# UPM_pcb_v1-0.net
KiCad netlist of a schematic drawn in EAGLE
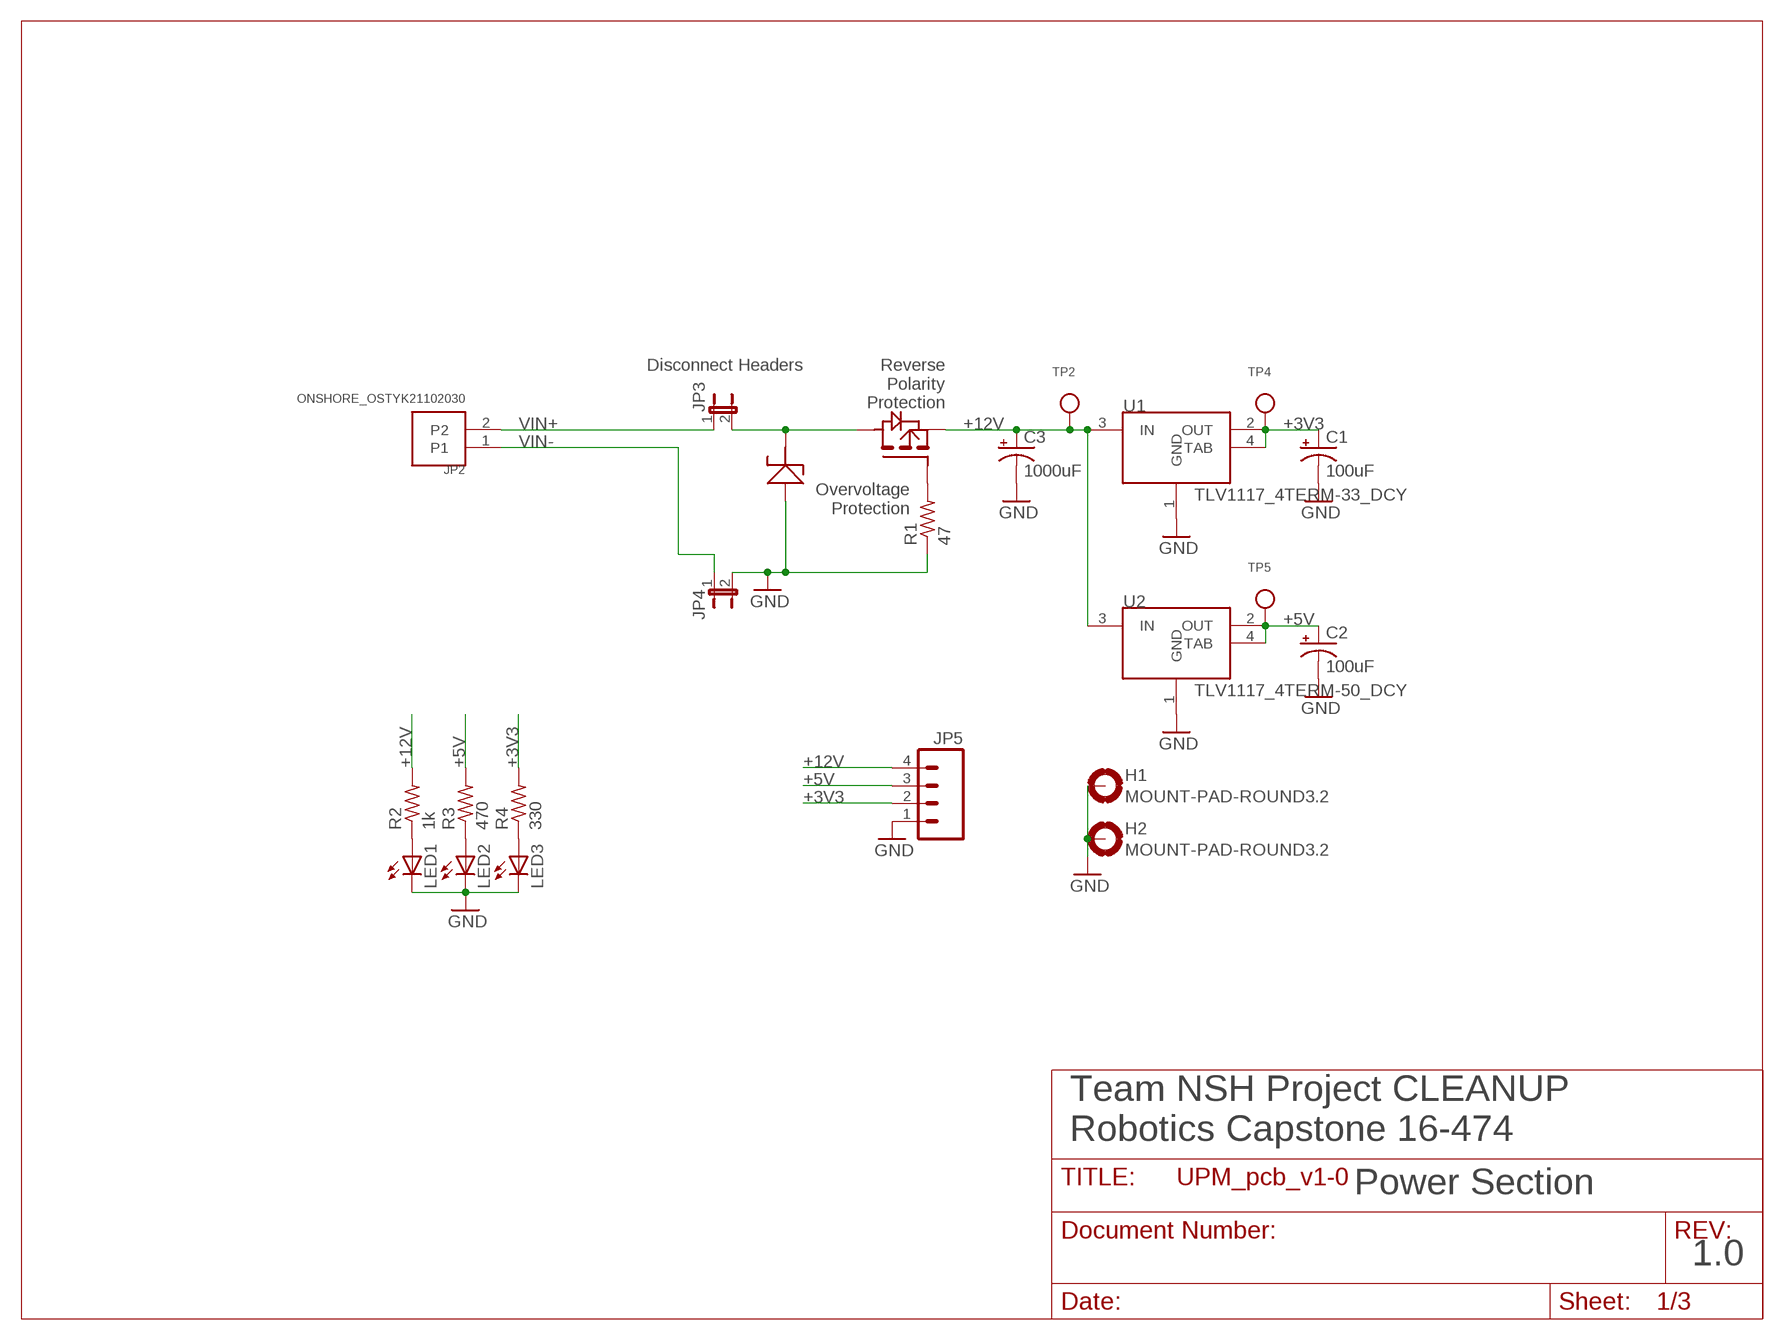
[diagram p0: schematic, sheet 1]
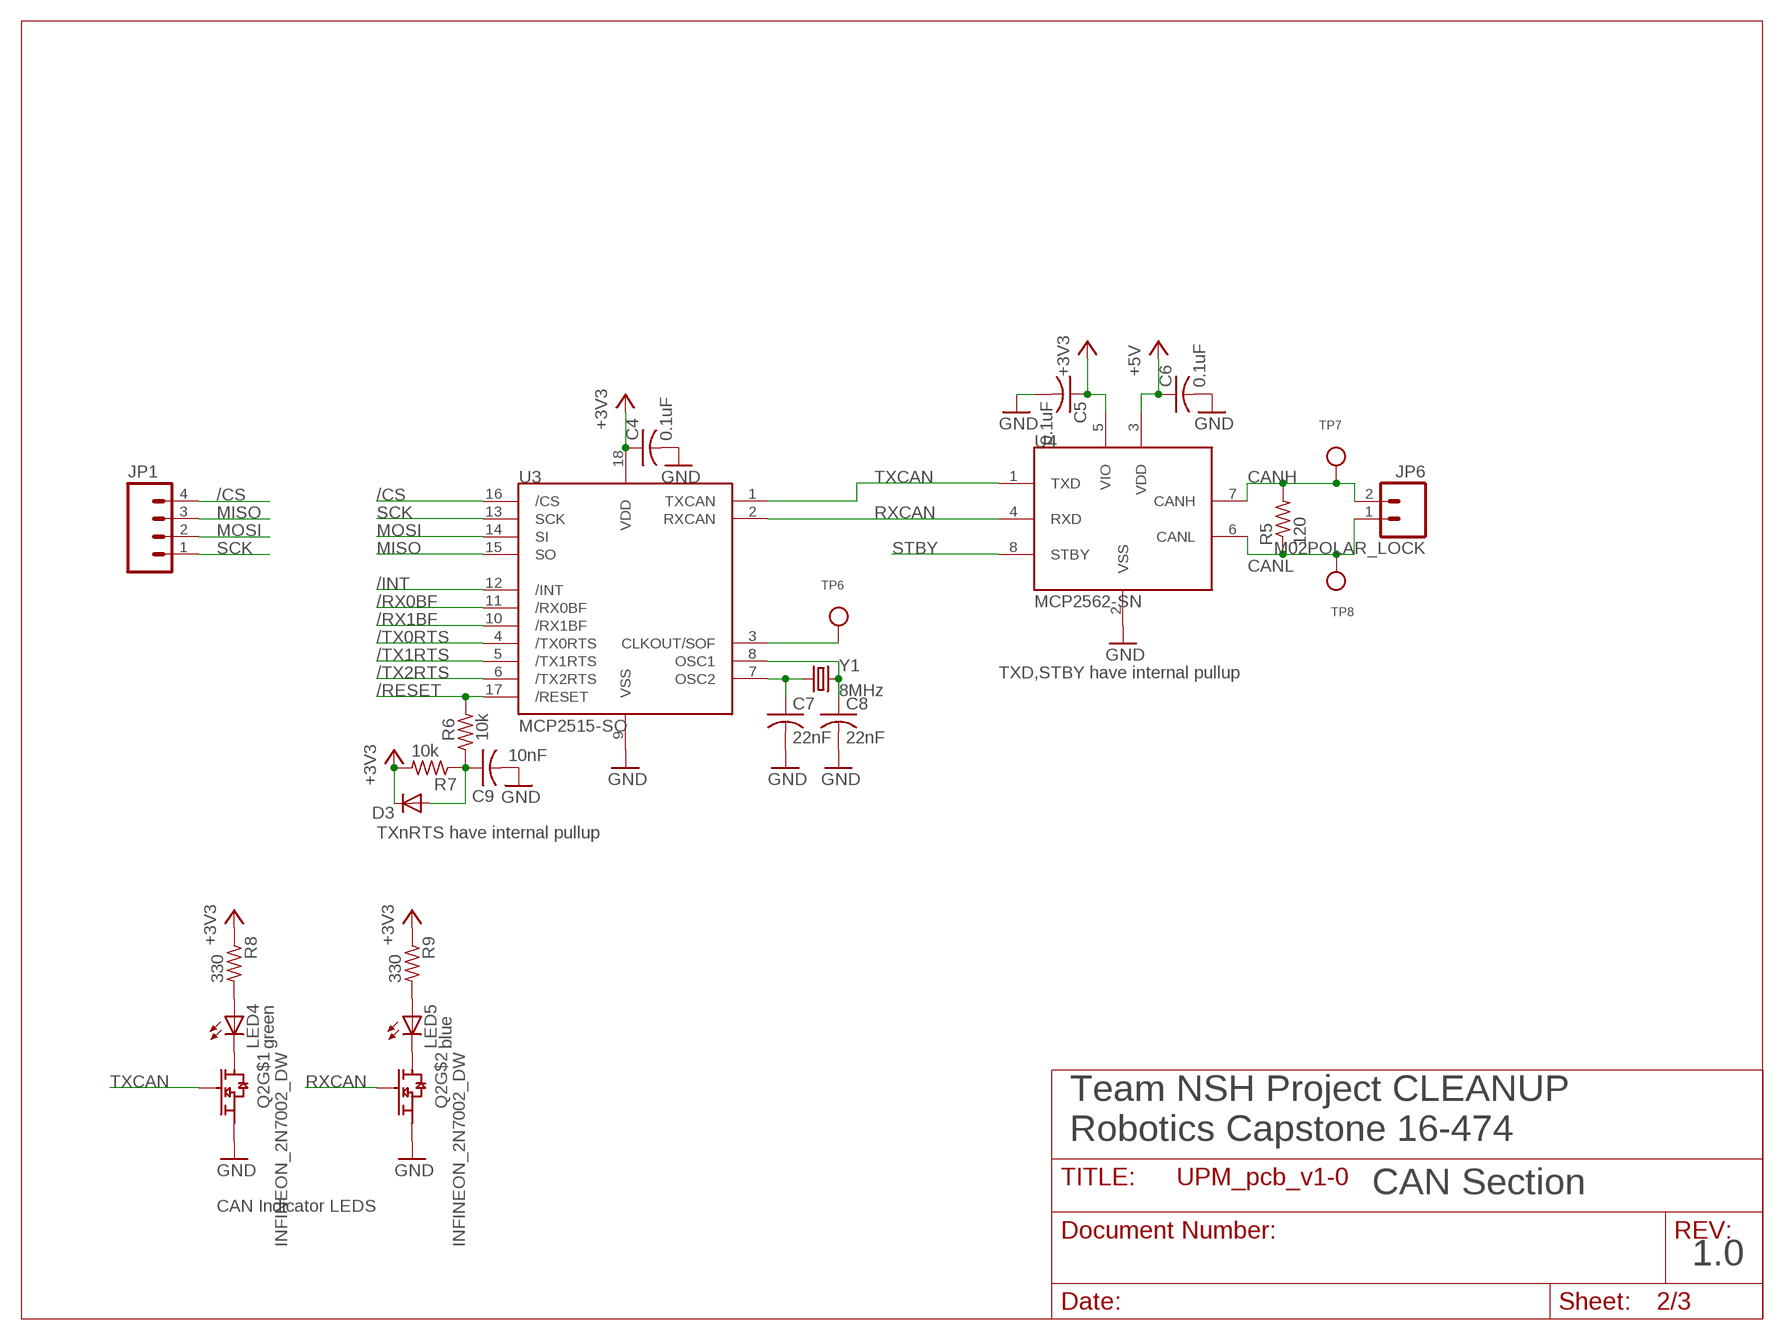
[diagram p1: schematic, sheet 2]
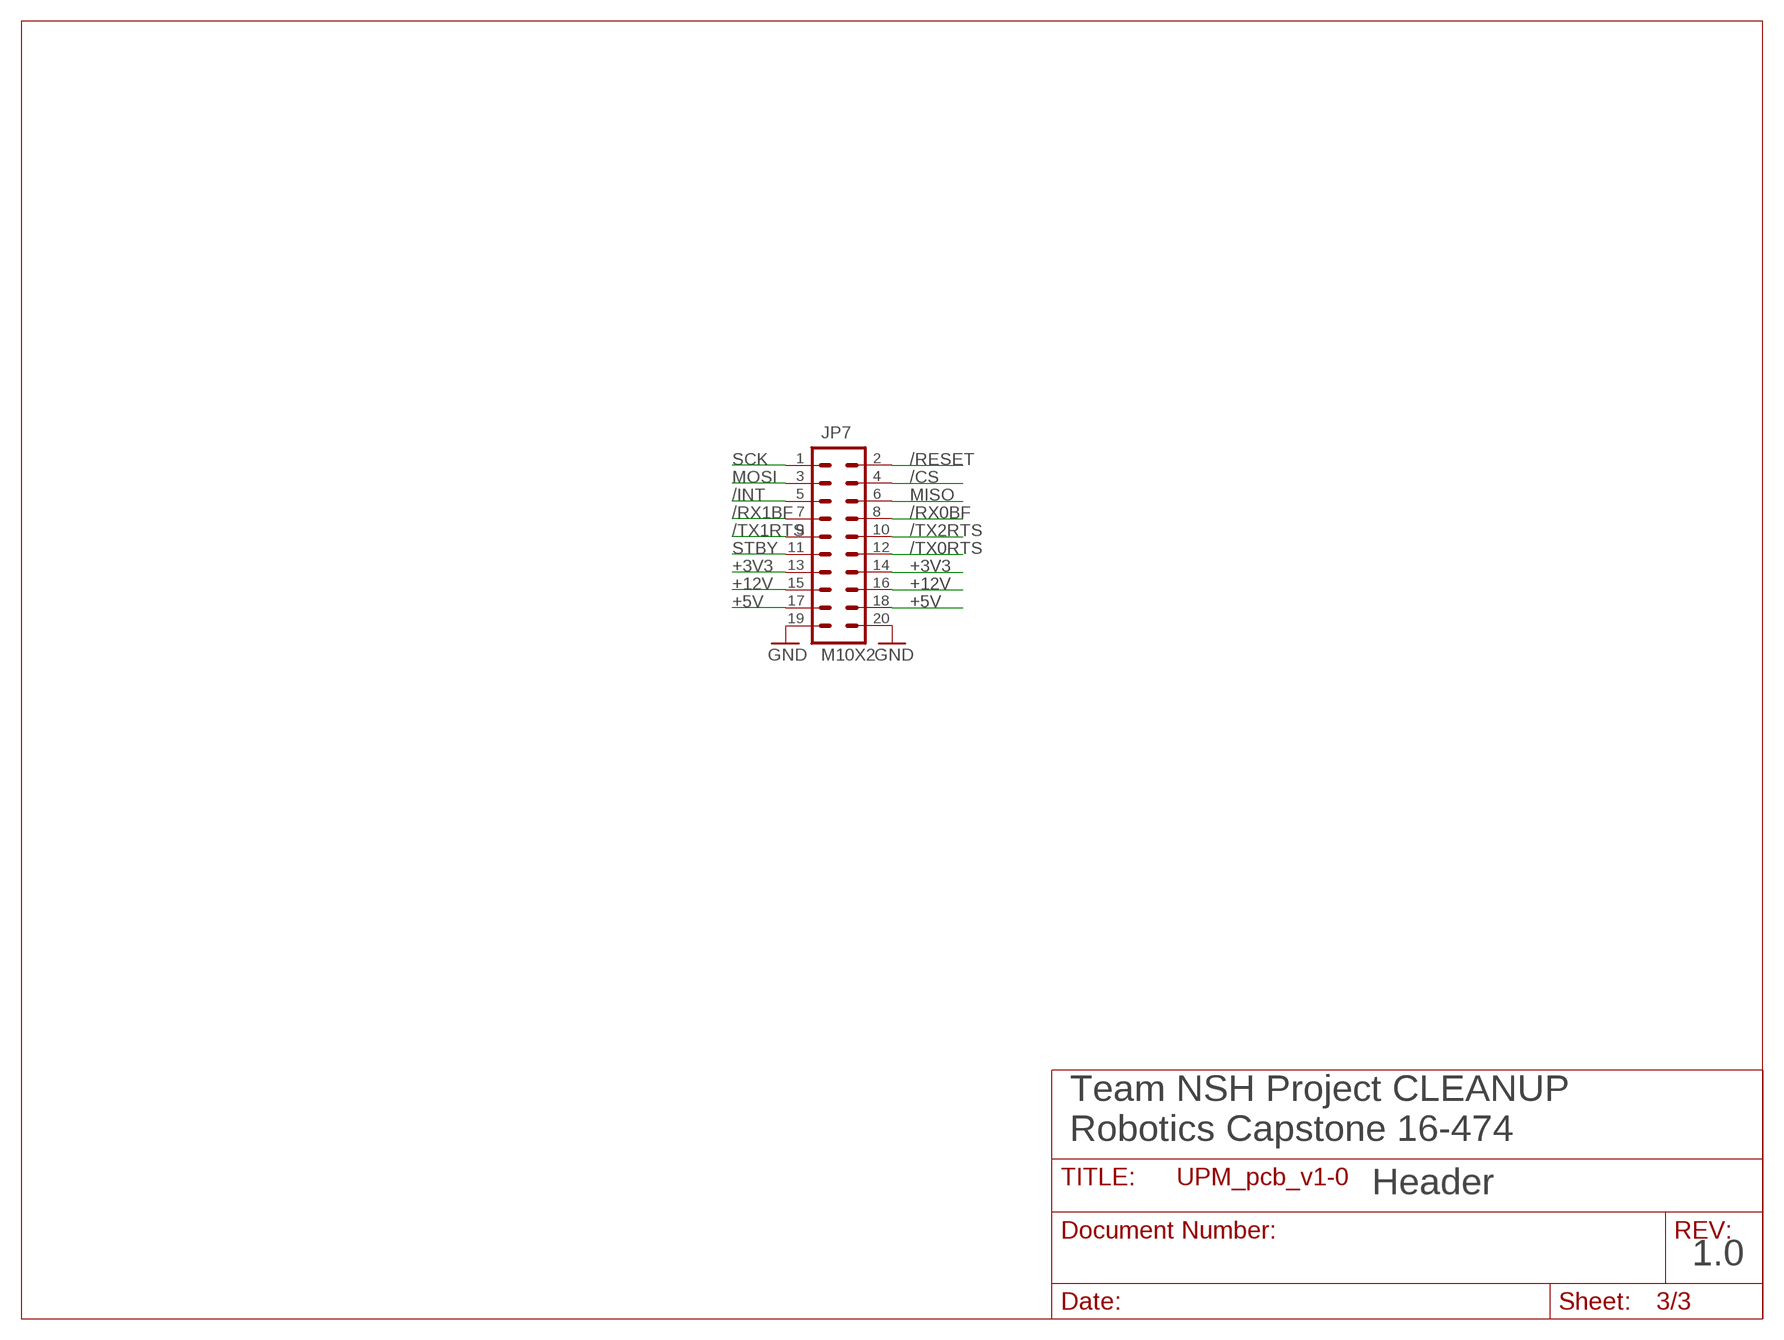
[diagram p2: schematic, sheet 3]

(export (version "E")
  (design (tool "Eeschema 10.0.6"))
  (components
    (comp (ref "C1")
      (value "100uF")
      (footprint "eagle-import:E2,5-5")
      (libsource (lib "eagle-import") (part "CPOL-USE2.5-5"))
    )
    (comp (ref "C2")
      (value "100uF")
      (footprint "eagle-import:E2,5-5")
      (libsource (lib "eagle-import") (part "CPOL-USE2.5-5"))
    )
    (comp (ref "C3")
      (value "1000uF")
      (footprint "eagle-import:E5-13")
      (libsource (lib "eagle-import") (part "CPOL-USE5-13"))
    )
    (comp (ref "D1")
      (value "VISHAY_SMA6F")
      (footprint "eagle-import:VSHY_DO-221AC")
      (libsource (lib "eagle-import") (part "VISHAY_SMA6F"))
    )
    (comp (ref "H1")
      (value "MOUNT-PAD-ROUND3.2")
      (footprint "eagle-import:3,2-PAD")
      (libsource (lib "eagle-import") (part "MOUNT-PAD-ROUND3.2"))
    )
    (comp (ref "H2")
      (value "MOUNT-PAD-ROUND3.2")
      (footprint "eagle-import:3,2-PAD")
      (libsource (lib "eagle-import") (part "MOUNT-PAD-ROUND3.2"))
    )
    (comp (ref "JP2")
      (value "ONSHORE_OSTYK21102030")
      (footprint "eagle-import:ONSHORE_OSTYK21102030")
      (libsource (lib "eagle-import") (part "ONSHORE_OSTYK21102030"))
    )
    (comp (ref "JP3")
      (value "JUMPER2")
      (footprint "eagle-import:JUMPER2")
      (libsource (lib "eagle-import") (part "JUMPER2"))
    )
    (comp (ref "JP4")
      (value "JUMPER2")
      (footprint "eagle-import:JUMPER2")
      (libsource (lib "eagle-import") (part "JUMPER2"))
    )
    (comp (ref "JP5")
      (value "M04LOCK")
      (footprint "eagle-import:1X04_LOCK")
      (libsource (lib "eagle-import") (part "M04LOCK"))
    )
    (comp (ref "LED1")
      (value "LED0603")
      (footprint "eagle-import:LED-0603")
      (libsource (lib "eagle-import") (part "LED0603"))
    )
    (comp (ref "LED2")
      (value "LED0603")
      (footprint "eagle-import:LED-0603")
      (libsource (lib "eagle-import") (part "LED0603"))
    )
    (comp (ref "LED3")
      (value "LED0603")
      (footprint "eagle-import:LED-0603")
      (libsource (lib "eagle-import") (part "LED0603"))
    )
    (comp (ref "Q1")
      (value "DMP4047SK3")
      (footprint "eagle-import:DIODES_TO252")
      (libsource (lib "eagle-import") (part "DMP4047SK3"))
    )
    (comp (ref "R1")
      (value "47")
      (footprint "eagle-import:R0603")
      (libsource (lib "eagle-import") (part "R-US_R0603"))
    )
    (comp (ref "R2")
      (value "1k")
      (footprint "eagle-import:R0603")
      (libsource (lib "eagle-import") (part "R-US_R0603"))
    )
    (comp (ref "R3")
      (value "470")
      (footprint "eagle-import:R0603")
      (libsource (lib "eagle-import") (part "R-US_R0603"))
    )
    (comp (ref "R4")
      (value "330")
      (footprint "eagle-import:R0603")
      (libsource (lib "eagle-import") (part "R-US_R0603"))
    )
    (comp (ref "TP2")
      (value "TESTPOINT0.1\"")
      (footprint "eagle-import:1X01_ROUND")
      (libsource (lib "eagle-import") (part "TESTPOINT0.1{dblquote}"))
    )
    (comp (ref "TP4")
      (value "TESTPOINT0.1\"")
      (footprint "eagle-import:1X01_ROUND")
      (libsource (lib "eagle-import") (part "TESTPOINT0.1{dblquote}"))
    )
    (comp (ref "TP5")
      (value "TESTPOINT0.1\"")
      (footprint "eagle-import:1X01_ROUND")
      (libsource (lib "eagle-import") (part "TESTPOINT0.1{dblquote}"))
    )
    (comp (ref "U1")
      (value "TLV1117_4TERM-33_DCY")
      (footprint "eagle-import:TI_SOT-223_DCY_R-PDSO-G4")
      (libsource (lib "eagle-import") (part "TLV1117_4TERM-33_DCY"))
    )
    (comp (ref "U2")
      (value "TLV1117_4TERM-50_DCY")
      (footprint "eagle-import:TI_SOT-223_DCY_R-PDSO-G4")
      (libsource (lib "eagle-import") (part "TLV1117_4TERM-50_DCY"))
    )
    (comp (ref "C4")
      (value "0.1uF")
      (footprint "eagle-import:C0603")
      (libsource (lib "eagle-import") (part "C-USC0603"))
    )
    (comp (ref "C5")
      (value "0.1uF")
      (footprint "eagle-import:C0603")
      (libsource (lib "eagle-import") (part "C-USC0603"))
    )
    (comp (ref "C6")
      (value "0.1uF")
      (footprint "eagle-import:C0603")
      (libsource (lib "eagle-import") (part "C-USC0603"))
    )
    (comp (ref "C7")
      (value "22nF")
      (footprint "eagle-import:C0603")
      (libsource (lib "eagle-import") (part "C-USC0603"))
    )
    (comp (ref "C8")
      (value "22nF")
      (footprint "eagle-import:C0603")
      (libsource (lib "eagle-import") (part "C-USC0603"))
    )
    (comp (ref "C9")
      (value "10nF")
      (footprint "eagle-import:C0603")
      (libsource (lib "eagle-import") (part "C-USC0603"))
    )
    (comp (ref "D3")
      (value "DIODE1N4148")
      (footprint "eagle-import:DIODE-1N4148")
      (libsource (lib "eagle-import") (part "DIODE1N4148"))
    )
    (comp (ref "JP1")
      (value "M04LOCK")
      (footprint "eagle-import:1X04_LOCK")
      (libsource (lib "eagle-import") (part "M04LOCK"))
    )
    (comp (ref "JP6")
      (value "M02POLAR_LOCK")
      (footprint "eagle-import:MOLEX-1X2_LOCK")
      (libsource (lib "eagle-import") (part "M02POLAR_LOCK"))
    )
    (comp (ref "LED4")
      (value "green")
      (footprint "eagle-import:LED-0603")
      (libsource (lib "eagle-import") (part "LED0603"))
    )
    (comp (ref "LED5")
      (value "blue")
      (footprint "eagle-import:LED-0603")
      (libsource (lib "eagle-import") (part "LED0603"))
    )
    (comp (ref "Q2")
      (value "INFINEON_2N7002_DW")
      (footprint "eagle-import:INFINEON_SOT363")
      (libsource (lib "eagle-import") (part "INFINEON_2N7002_DW"))
    )
    (comp (ref "R5")
      (value "120")
      (footprint "eagle-import:R0603")
      (libsource (lib "eagle-import") (part "R-US_R0603"))
    )
    (comp (ref "R6")
      (value "10k")
      (footprint "eagle-import:R0603")
      (libsource (lib "eagle-import") (part "R-US_R0603"))
    )
    (comp (ref "R7")
      (value "10k")
      (footprint "eagle-import:R0603")
      (libsource (lib "eagle-import") (part "R-US_R0603"))
    )
    (comp (ref "R8")
      (value "330")
      (footprint "eagle-import:R0603")
      (libsource (lib "eagle-import") (part "R-US_R0603"))
    )
    (comp (ref "R9")
      (value "330")
      (footprint "eagle-import:R0603")
      (libsource (lib "eagle-import") (part "R-US_R0603"))
    )
    (comp (ref "TP6")
      (value "TESTPOINT0.1\"")
      (footprint "eagle-import:1X01_ROUND")
      (libsource (lib "eagle-import") (part "TESTPOINT0.1{dblquote}"))
    )
    (comp (ref "TP7")
      (value "TESTPOINT0.1\"")
      (footprint "eagle-import:1X01_ROUND")
      (libsource (lib "eagle-import") (part "TESTPOINT0.1{dblquote}"))
    )
    (comp (ref "TP8")
      (value "TESTPOINT0.1\"")
      (footprint "eagle-import:1X01_ROUND")
      (libsource (lib "eagle-import") (part "TESTPOINT0.1{dblquote}"))
    )
    (comp (ref "U3")
      (value "MCP2515-SO")
      (footprint "eagle-import:MCP_SO_SOIC-18")
      (libsource (lib "eagle-import") (part "MCP2515-SO"))
    )
    (comp (ref "U4")
      (value "MCP2562-SN")
      (footprint "eagle-import:MCP_SN_SOIC-8")
      (libsource (lib "eagle-import") (part "MCP2562-SN"))
    )
    (comp (ref "Y1")
      (value "8MHz")
      (footprint "eagle-import:HC49U-V")
      (libsource (lib "eagle-import") (part "CRYSTALHC49UV"))
    )
    (comp (ref "JP7")
      (value "M10X2")
      (footprint "eagle-import:2X10")
      (libsource (lib "eagle-import") (part "M10X2"))
    )
  )
  (nets
    (net (code "1") (name "+3V3") (class "Default")
      (node (ref "C1") (pin "+") (pinfunction "+_+") (pintype "passive"))
      (node (ref "C4") (pin "1") (pinfunction "1_1") (pintype "passive"))
      (node (ref "C5") (pin "1") (pinfunction "1_1") (pintype "passive"))
      (node (ref "D3") (pin "C") (pinfunction "C_C") (pintype "passive"))
      (node (ref "JP5") (pin "2") (pinfunction "2_2") (pintype "passive"))
      (node (ref "JP7") (pin "13") (pinfunction "13_13") (pintype "passive"))
      (node (ref "JP7") (pin "14") (pinfunction "14_14") (pintype "passive"))
      (node (ref "R4") (pin "2") (pinfunction "2_2") (pintype "passive"))
      (node (ref "R7") (pin "2") (pinfunction "2_2") (pintype "passive"))
      (node (ref "R8") (pin "1") (pinfunction "1_1") (pintype "passive"))
      (node (ref "R9") (pin "1") (pinfunction "1_1") (pintype "passive"))
      (node (ref "TP4") (pin "1") (pinfunction "P$1_1") (pintype "bidirectional"))
      (node (ref "U1") (pin "2") (pinfunction "OUT_2") (pintype "bidirectional"))
      (node (ref "U1") (pin "4") (pinfunction "TAB_4") (pintype "bidirectional"))
      (node (ref "U3") (pin "18") (pinfunction "VDD_18") (pintype "bidirectional"))
      (node (ref "U4") (pin "5") (pinfunction "VIO_5") (pintype "bidirectional"))
    )
    (net (code "2") (name "+5V") (class "Default")
      (node (ref "C2") (pin "+") (pinfunction "+_+") (pintype "passive"))
      (node (ref "C6") (pin "1") (pinfunction "1_1") (pintype "passive"))
      (node (ref "JP5") (pin "3") (pinfunction "3_3") (pintype "passive"))
      (node (ref "JP7") (pin "17") (pinfunction "17_17") (pintype "passive"))
      (node (ref "JP7") (pin "18") (pinfunction "18_18") (pintype "passive"))
      (node (ref "R3") (pin "2") (pinfunction "2_2") (pintype "passive"))
      (node (ref "TP5") (pin "1") (pinfunction "P$1_1") (pintype "bidirectional"))
      (node (ref "U2") (pin "2") (pinfunction "OUT_2") (pintype "bidirectional"))
      (node (ref "U2") (pin "4") (pinfunction "TAB_4") (pintype "bidirectional"))
      (node (ref "U4") (pin "3") (pinfunction "VDD_3") (pintype "bidirectional"))
    )
    (net (code "3") (name "+12V") (class "Default")
      (node (ref "C3") (pin "+") (pinfunction "+_+") (pintype "passive"))
      (node (ref "JP5") (pin "4") (pinfunction "4_4") (pintype "passive"))
      (node (ref "JP7") (pin "15") (pinfunction "15_15") (pintype "passive"))
      (node (ref "JP7") (pin "16") (pinfunction "16_16") (pintype "passive"))
      (node (ref "Q1") (pin "2") (pinfunction "S_2") (pintype "bidirectional"))
      (node (ref "R2") (pin "2") (pinfunction "2_2") (pintype "passive"))
      (node (ref "TP2") (pin "1") (pinfunction "P$1_1") (pintype "bidirectional"))
      (node (ref "U1") (pin "3") (pinfunction "IN_3") (pintype "bidirectional"))
      (node (ref "U2") (pin "3") (pinfunction "IN_3") (pintype "bidirectional"))
    )
    (net (code "4") (name "CANH") (class "Default")
      (node (ref "JP6") (pin "2") (pinfunction "2_2") (pintype "passive"))
      (node (ref "R5") (pin "2") (pinfunction "2_2") (pintype "passive"))
      (node (ref "TP7") (pin "1") (pinfunction "P$1_1") (pintype "bidirectional"))
      (node (ref "U4") (pin "7") (pinfunction "CANH_7") (pintype "bidirectional"))
    )
    (net (code "5") (name "CANL") (class "Default")
      (node (ref "JP6") (pin "1") (pinfunction "1_1") (pintype "passive"))
      (node (ref "R5") (pin "1") (pinfunction "1_1") (pintype "passive"))
      (node (ref "TP8") (pin "1") (pinfunction "P$1_1") (pintype "bidirectional"))
      (node (ref "U4") (pin "6") (pinfunction "CANL_6") (pintype "bidirectional"))
    )
    (net (code "6") (name "GND") (class "Default")
      (node (ref "C1") (pin "-") (pinfunction "-_-") (pintype "passive"))
      (node (ref "C2") (pin "-") (pinfunction "-_-") (pintype "passive"))
      (node (ref "C3") (pin "-") (pinfunction "-_-") (pintype "passive"))
      (node (ref "C4") (pin "2") (pinfunction "2_2") (pintype "passive"))
      (node (ref "C5") (pin "2") (pinfunction "2_2") (pintype "passive"))
      (node (ref "C6") (pin "2") (pinfunction "2_2") (pintype "passive"))
      (node (ref "C7") (pin "2") (pinfunction "2_2") (pintype "passive"))
      (node (ref "C8") (pin "2") (pinfunction "2_2") (pintype "passive"))
      (node (ref "C9") (pin "2") (pinfunction "2_2") (pintype "passive"))
      (node (ref "D1") (pin "A") (pinfunction "A_A") (pintype "bidirectional"))
      (node (ref "H1") (pin "B3,2") (pinfunction "MOUNT_B3,2") (pintype "passive"))
      (node (ref "H2") (pin "B3,2") (pinfunction "MOUNT_B3,2") (pintype "passive"))
      (node (ref "JP4") (pin "2") (pinfunction "2_2") (pintype "passive"))
      (node (ref "JP5") (pin "1") (pinfunction "1_1") (pintype "passive"))
      (node (ref "JP7") (pin "19") (pinfunction "19_19") (pintype "passive"))
      (node (ref "JP7") (pin "20") (pinfunction "20_20") (pintype "passive"))
      (node (ref "LED1") (pin "C") (pinfunction "C_C") (pintype "passive"))
      (node (ref "LED2") (pin "C") (pinfunction "C_C") (pintype "passive"))
      (node (ref "LED3") (pin "C") (pinfunction "C_C") (pintype "passive"))
      (node (ref "Q2") (pin "1") (pinfunction "SOURCE_1") (pintype "bidirectional"))
      (node (ref "Q2") (pin "4") (pinfunction "SOURCE_4") (pintype "bidirectional"))
      (node (ref "R1") (pin "1") (pinfunction "1_1") (pintype "passive"))
      (node (ref "U1") (pin "1") (pinfunction "GND_1") (pintype "bidirectional"))
      (node (ref "U2") (pin "1") (pinfunction "GND_1") (pintype "bidirectional"))
      (node (ref "U3") (pin "9") (pinfunction "VSS_9") (pintype "bidirectional"))
      (node (ref "U4") (pin "2") (pinfunction "VSS_2") (pintype "bidirectional"))
    )
    (net (code "7") (name "MISO") (class "Default")
      (node (ref "JP1") (pin "3") (pinfunction "3_3") (pintype "passive"))
      (node (ref "JP7") (pin "6") (pinfunction "6_6") (pintype "passive"))
      (node (ref "U3") (pin "15") (pinfunction "SO_15") (pintype "bidirectional"))
    )
    (net (code "8") (name "MOSI") (class "Default")
      (node (ref "JP1") (pin "2") (pinfunction "2_2") (pintype "passive"))
      (node (ref "JP7") (pin "3") (pinfunction "3_3") (pintype "passive"))
      (node (ref "U3") (pin "14") (pinfunction "SI_14") (pintype "bidirectional"))
    )
    (net (code "9") (name "Net-(C9-Pad1)") (class "Default")
      (node (ref "C9") (pin "1") (pinfunction "1_1") (pintype "passive"))
      (node (ref "D3") (pin "A") (pinfunction "A_A") (pintype "passive"))
      (node (ref "R6") (pin "1") (pinfunction "1_1") (pintype "passive"))
      (node (ref "R7") (pin "1") (pinfunction "1_1") (pintype "passive"))
    )
    (net (code "10") (name "Net-(LED1-PadA)") (class "Default")
      (node (ref "LED1") (pin "A") (pinfunction "A_A") (pintype "passive"))
      (node (ref "R2") (pin "1") (pinfunction "1_1") (pintype "passive"))
    )
    (net (code "11") (name "Net-(LED2-PadA)") (class "Default")
      (node (ref "LED2") (pin "A") (pinfunction "A_A") (pintype "passive"))
      (node (ref "R3") (pin "1") (pinfunction "1_1") (pintype "passive"))
    )
    (net (code "12") (name "Net-(LED3-PadA)") (class "Default")
      (node (ref "LED3") (pin "A") (pinfunction "A_A") (pintype "passive"))
      (node (ref "R4") (pin "1") (pinfunction "1_1") (pintype "passive"))
    )
    (net (code "13") (name "Net-(LED4-PadA)") (class "Default")
      (node (ref "LED4") (pin "A") (pinfunction "A_A") (pintype "passive"))
      (node (ref "R8") (pin "2") (pinfunction "2_2") (pintype "passive"))
    )
    (net (code "14") (name "Net-(LED5-PadA)") (class "Default")
      (node (ref "LED5") (pin "A") (pinfunction "A_A") (pintype "passive"))
      (node (ref "R9") (pin "2") (pinfunction "2_2") (pintype "passive"))
    )
    (net (code "15") (name "Net-(Q1-D)") (class "Default")
      (node (ref "D1") (pin "K") (pinfunction "K_K") (pintype "bidirectional"))
      (node (ref "JP3") (pin "2") (pinfunction "2_2") (pintype "passive"))
      (node (ref "Q1") (pin "3") (pinfunction "D_3") (pintype "bidirectional"))
    )
    (net (code "16") (name "Net-(Q1-G)") (class "Default")
      (node (ref "Q1") (pin "1") (pinfunction "G_1") (pintype "bidirectional"))
      (node (ref "R1") (pin "2") (pinfunction "2_2") (pintype "passive"))
    )
    (net (code "17") (name "Net-(Q2A-DRAIN)") (class "Default")
      (node (ref "LED4") (pin "C") (pinfunction "C_C") (pintype "passive"))
      (node (ref "Q2") (pin "6") (pinfunction "DRAIN_6") (pintype "bidirectional"))
    )
    (net (code "18") (name "Net-(Q2B-DRAIN)") (class "Default")
      (node (ref "LED5") (pin "C") (pinfunction "C_C") (pintype "passive"))
      (node (ref "Q2") (pin "3") (pinfunction "DRAIN_3") (pintype "bidirectional"))
    )
    (net (code "19") (name "Net-(TP6-P$1)") (class "Default")
      (node (ref "TP6") (pin "1") (pinfunction "P$1_1") (pintype "bidirectional"))
      (node (ref "U3") (pin "3") (pinfunction "CLKOUT/SOF_3") (pintype "bidirectional"))
    )
    (net (code "20") (name "Net-(U3-OSC1)") (class "Default")
      (node (ref "C8") (pin "1") (pinfunction "1_1") (pintype "passive"))
      (node (ref "U3") (pin "8") (pinfunction "OSC1_8") (pintype "bidirectional"))
      (node (ref "Y1") (pin "2") (pinfunction "2_2") (pintype "passive"))
    )
    (net (code "21") (name "Net-(U3-OSC2)") (class "Default")
      (node (ref "C7") (pin "1") (pinfunction "1_1") (pintype "passive"))
      (node (ref "U3") (pin "7") (pinfunction "OSC2_7") (pintype "bidirectional"))
      (node (ref "Y1") (pin "1") (pinfunction "1_1") (pintype "passive"))
    )
    (net (code "22") (name "RXCAN") (class "Default")
      (node (ref "Q2") (pin "5") (pinfunction "GATE_5") (pintype "bidirectional"))
      (node (ref "U3") (pin "2") (pinfunction "RXCAN_2") (pintype "bidirectional"))
      (node (ref "U4") (pin "4") (pinfunction "RXD_4") (pintype "bidirectional"))
    )
    (net (code "23") (name "SCK") (class "Default")
      (node (ref "JP1") (pin "1") (pinfunction "1_1") (pintype "passive"))
      (node (ref "JP7") (pin "1") (pinfunction "1_1") (pintype "passive"))
      (node (ref "U3") (pin "13") (pinfunction "SCK_13") (pintype "bidirectional"))
    )
    (net (code "24") (name "STBY") (class "Default")
      (node (ref "JP7") (pin "11") (pinfunction "11_11") (pintype "passive"))
      (node (ref "U4") (pin "8") (pinfunction "STBY_8") (pintype "bidirectional"))
    )
    (net (code "25") (name "TXCAN") (class "Default")
      (node (ref "Q2") (pin "2") (pinfunction "GATE_2") (pintype "bidirectional"))
      (node (ref "U3") (pin "1") (pinfunction "TXCAN_1") (pintype "bidirectional"))
      (node (ref "U4") (pin "1") (pinfunction "TXD_1") (pintype "bidirectional"))
    )
    (net (code "26") (name "VIN+") (class "Default")
      (node (ref "JP2") (pin "2") (pinfunction "P2_2") (pintype "bidirectional"))
      (node (ref "JP3") (pin "1") (pinfunction "1_1") (pintype "passive"))
    )
    (net (code "27") (name "VIN-") (class "Default")
      (node (ref "JP2") (pin "1") (pinfunction "P1_1") (pintype "bidirectional"))
      (node (ref "JP4") (pin "1") (pinfunction "1_1") (pintype "passive"))
    )
    (net (code "28") (name "{slash}CS") (class "Default")
      (node (ref "JP1") (pin "4") (pinfunction "4_4") (pintype "passive"))
      (node (ref "JP7") (pin "4") (pinfunction "4_4") (pintype "passive"))
      (node (ref "U3") (pin "16") (pinfunction "/CS_16") (pintype "bidirectional"))
    )
    (net (code "29") (name "{slash}INT") (class "Default")
      (node (ref "JP7") (pin "5") (pinfunction "5_5") (pintype "passive"))
      (node (ref "U3") (pin "12") (pinfunction "/INT_12") (pintype "bidirectional"))
    )
    (net (code "30") (name "{slash}RESET") (class "Default")
      (node (ref "JP7") (pin "2") (pinfunction "2_2") (pintype "passive"))
      (node (ref "R6") (pin "2") (pinfunction "2_2") (pintype "passive"))
      (node (ref "U3") (pin "17") (pinfunction "/RESET_17") (pintype "bidirectional"))
    )
    (net (code "31") (name "{slash}RX0BF") (class "Default")
      (node (ref "JP7") (pin "8") (pinfunction "8_8") (pintype "passive"))
      (node (ref "U3") (pin "11") (pinfunction "/RX0BF_11") (pintype "bidirectional"))
    )
    (net (code "32") (name "{slash}RX1BF") (class "Default")
      (node (ref "JP7") (pin "7") (pinfunction "7_7") (pintype "passive"))
      (node (ref "U3") (pin "10") (pinfunction "/RX1BF_10") (pintype "bidirectional"))
    )
    (net (code "33") (name "{slash}TX0RTS") (class "Default")
      (node (ref "JP7") (pin "12") (pinfunction "12_12") (pintype "passive"))
      (node (ref "U3") (pin "4") (pinfunction "/TX0RTS_4") (pintype "bidirectional"))
    )
    (net (code "34") (name "{slash}TX1RTS") (class "Default")
      (node (ref "JP7") (pin "9") (pinfunction "9_9") (pintype "passive"))
      (node (ref "U3") (pin "5") (pinfunction "/TX1RTS_5") (pintype "bidirectional"))
    )
    (net (code "35") (name "{slash}TX2RTS") (class "Default")
      (node (ref "JP7") (pin "10") (pinfunction "10_10") (pintype "passive"))
      (node (ref "U3") (pin "6") (pinfunction "/TX2RTS_6") (pintype "bidirectional"))
    )
  )
)
